# pot-boardB.net
KiCad netlist of a schematic drawn in EAGLE
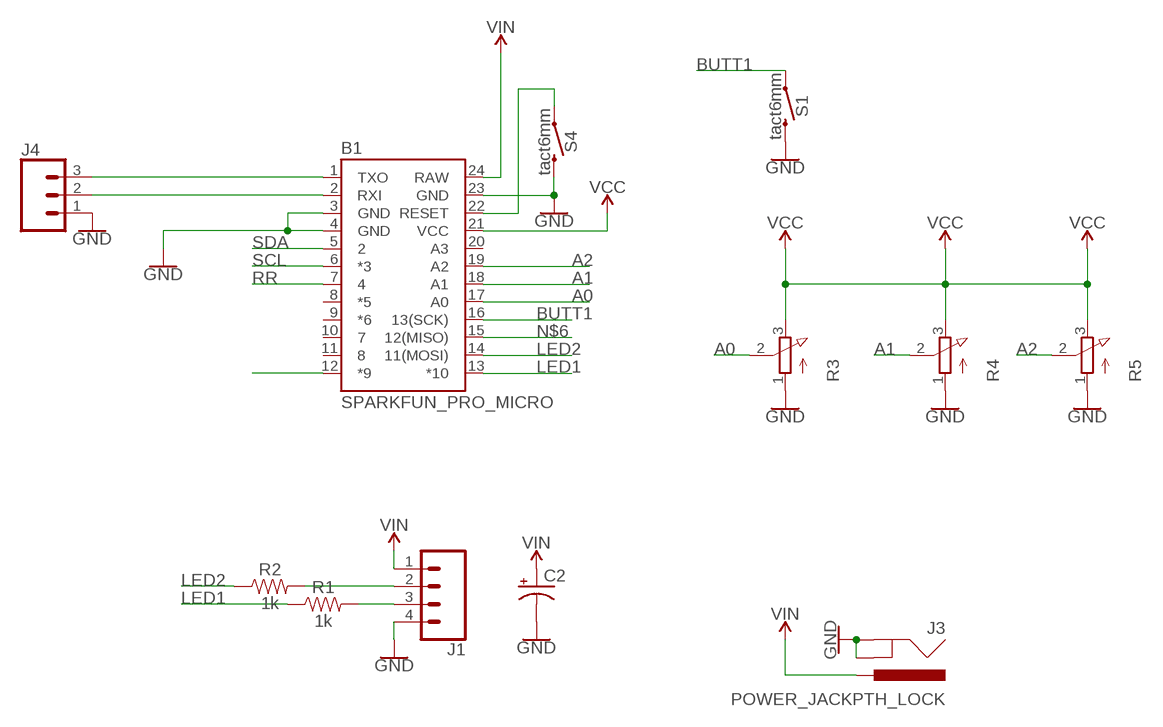
[diagram p0: schematic, sheet 1]

(export (version "E")
  (design (tool "Eeschema 10.0.6"))
  (components
    (comp (ref "B1")
      (value "SPARKFUN_PRO_MICRO")
      (footprint "eagle-import:SPARKFUN_PRO_MICRO")
      (libsource (lib "eagle-import") (part "SPARKFUN_PRO_MICRO"))
    )
    (comp (ref "C2")
      (value "CPOL-USE3.5-8")
      (footprint "eagle-import:E3,5-8")
      (libsource (lib "eagle-import") (part "CPOL-USE3.5-8"))
    )
    (comp (ref "J1")
      (value "CONN_04")
      (footprint "eagle-import:1X04")
      (libsource (lib "eagle-import") (part "CONN_04"))
    )
    (comp (ref "J3")
      (value "POWER_JACKPTH_LOCK")
      (footprint "eagle-import:POWER_JACK_PTH_LOCK")
      (libsource (lib "eagle-import") (part "POWER_JACKPTH_LOCK"))
    )
    (comp (ref "J4")
      (value "CONN_03")
      (footprint "eagle-import:1X03")
      (libsource (lib "eagle-import") (part "CONN_03"))
    )
    (comp (ref "R1")
      (value "1k")
      (footprint "eagle-import:AXIAL-0.3")
      (libsource (lib "eagle-import") (part "1KOHM-HORIZ-1/4W-5%"))
    )
    (comp (ref "R2")
      (value "1k")
      (footprint "eagle-import:AXIAL-0.3")
      (libsource (lib "eagle-import") (part "1KOHM-HORIZ-1/4W-5%"))
    )
    (comp (ref "R3")
      (value "3RP/1610N")
      (footprint "eagle-import:3RP_1610N")
      (libsource (lib "eagle-import") (part "3RP/1610N"))
    )
    (comp (ref "R4")
      (value "3RP/1610N")
      (footprint "eagle-import:3RP_1610N")
      (libsource (lib "eagle-import") (part "3RP/1610N"))
    )
    (comp (ref "R5")
      (value "3RP/1610N")
      (footprint "eagle-import:3RP_1610N")
      (libsource (lib "eagle-import") (part "3RP/1610N"))
    )
    (comp (ref "S1")
      (value "tact6mm")
      (footprint "eagle-import:TACTILE_SWITCH_PTH_6.0MM")
      (libsource (lib "eagle-import") (part "MOMENTARY-SWITCH-SPST-PTH-6.0MM"))
    )
    (comp (ref "S4")
      (value "tact6mm")
      (footprint "eagle-import:TACTILE_SWITCH_PTH_6.0MM")
      (libsource (lib "eagle-import") (part "MOMENTARY-SWITCH-SPST-PTH-6.0MM"))
    )
  )
  (nets
    (net (code "1") (name "/A0") (class "Default")
      (node (ref "B1") (pin "17") (pinfunction "A0_17") (pintype "bidirectional"))
      (node (ref "R3") (pin "2") (pinfunction "S_2") (pintype "passive"))
    )
    (net (code "2") (name "/A1") (class "Default")
      (node (ref "B1") (pin "18") (pinfunction "A1_18") (pintype "bidirectional"))
      (node (ref "R4") (pin "2") (pinfunction "S_2") (pintype "passive"))
    )
    (net (code "3") (name "/A2") (class "Default")
      (node (ref "B1") (pin "19") (pinfunction "A2_19") (pintype "bidirectional"))
      (node (ref "R5") (pin "2") (pinfunction "S_2") (pintype "passive"))
    )
    (net (code "4") (name "/BUTT1") (class "Default")
      (node (ref "B1") (pin "16") (pinfunction "13(SCK)_16") (pintype "bidirectional"))
      (node (ref "S1") (pin "1") (pinfunction "1_1") (pintype "passive"))
    )
    (net (code "5") (name "/LED1") (class "Default")
      (node (ref "B1") (pin "13") (pinfunction "*10_13") (pintype "bidirectional"))
      (node (ref "R1") (pin "P$1") (pinfunction "1_P$1") (pintype "passive"))
    )
    (net (code "6") (name "/LED2") (class "Default")
      (node (ref "B1") (pin "14") (pinfunction "11(MOSI)_14") (pintype "bidirectional"))
      (node (ref "R2") (pin "P$1") (pinfunction "1_P$1") (pintype "passive"))
    )
    (net (code "7") (name "/N$6") (class "Default")
      (node (ref "B1") (pin "15") (pinfunction "12(MISO)_15") (pintype "bidirectional"))
    )
    (net (code "8") (name "/RR") (class "Default")
      (node (ref "B1") (pin "7") (pinfunction "4_7") (pintype "bidirectional"))
    )
    (net (code "9") (name "/SCL") (class "Default")
      (node (ref "B1") (pin "6") (pinfunction "*3_6") (pintype "bidirectional"))
    )
    (net (code "10") (name "/SDA") (class "Default")
      (node (ref "B1") (pin "5") (pinfunction "2_5") (pintype "bidirectional"))
    )
    (net (code "11") (name "GND") (class "Default")
      (node (ref "B1") (pin "23") (pinfunction "GND_23") (pintype "power_in"))
      (node (ref "B1") (pin "3") (pinfunction "GND_3") (pintype "power_in"))
      (node (ref "B1") (pin "4") (pinfunction "GND_4") (pintype "power_in"))
      (node (ref "C2") (pin "-") (pinfunction "-_-") (pintype "passive"))
      (node (ref "J1") (pin "4") (pinfunction "4_4") (pintype "passive"))
      (node (ref "J3") (pin "GND") (pinfunction "GND_GND") (pintype "bidirectional"))
      (node (ref "J3") (pin "GNDBREAK") (pinfunction "GNDBREAK_GNDBREAK") (pintype "bidirectional"))
      (node (ref "J4") (pin "1") (pinfunction "1_1") (pintype "passive"))
      (node (ref "R3") (pin "1") (pinfunction "A_1") (pintype "passive"))
      (node (ref "R4") (pin "1") (pinfunction "A_1") (pintype "passive"))
      (node (ref "R5") (pin "1") (pinfunction "A_1") (pintype "passive"))
      (node (ref "S1") (pin "3") (pinfunction "2_3") (pintype "passive"))
      (node (ref "S4") (pin "3") (pinfunction "2_3") (pintype "passive"))
    )
    (net (code "12") (name "Net-(B1-RESET)") (class "Default")
      (node (ref "B1") (pin "22") (pinfunction "RESET_22") (pintype "bidirectional"))
      (node (ref "S4") (pin "1") (pinfunction "1_1") (pintype "passive"))
    )
    (net (code "13") (name "Net-(B1-RXI)") (class "Default")
      (node (ref "B1") (pin "2") (pinfunction "RXI_2") (pintype "bidirectional"))
      (node (ref "J4") (pin "2") (pinfunction "2_2") (pintype "passive"))
    )
    (net (code "14") (name "Net-(B1-TXO)") (class "Default")
      (node (ref "B1") (pin "1") (pinfunction "TXO_1") (pintype "bidirectional"))
      (node (ref "J4") (pin "3") (pinfunction "3_3") (pintype "passive"))
    )
    (net (code "15") (name "Net-(R1-2)") (class "Default")
      (node (ref "J1") (pin "3") (pinfunction "3_3") (pintype "passive"))
      (node (ref "R1") (pin "P$2") (pinfunction "2_P$2") (pintype "passive"))
    )
    (net (code "16") (name "Net-(R2-2)") (class "Default")
      (node (ref "J1") (pin "2") (pinfunction "2_2") (pintype "passive"))
      (node (ref "R2") (pin "P$2") (pinfunction "2_P$2") (pintype "passive"))
    )
    (net (code "17") (name "VCC") (class "Default")
      (node (ref "B1") (pin "21") (pinfunction "VCC_21") (pintype "power_in"))
      (node (ref "R3") (pin "3") (pinfunction "E_3") (pintype "passive"))
      (node (ref "R4") (pin "3") (pinfunction "E_3") (pintype "passive"))
      (node (ref "R5") (pin "3") (pinfunction "E_3") (pintype "passive"))
    )
    (net (code "18") (name "VIN") (class "Default")
      (node (ref "B1") (pin "24") (pinfunction "RAW_24") (pintype "power_in"))
      (node (ref "C2") (pin "+") (pinfunction "+_+") (pintype "passive"))
      (node (ref "J1") (pin "1") (pinfunction "1_1") (pintype "passive"))
      (node (ref "J3") (pin "PWR") (pinfunction "PWR_PWR") (pintype "bidirectional"))
    )
    (net (code "19") (name "unconnected-(B1-*5-Pad8)") (class "Default")
      (node (ref "B1") (pin "8") (pinfunction "*5_8") (pintype "bidirectional"))
    )
    (net (code "20") (name "unconnected-(B1-*6-Pad9)") (class "Default")
      (node (ref "B1") (pin "9") (pinfunction "*6_9") (pintype "bidirectional"))
    )
    (net (code "21") (name "unconnected-(B1-*9-Pad12)") (class "Default")
      (node (ref "B1") (pin "12") (pinfunction "*9_12") (pintype "bidirectional"))
    )
    (net (code "22") (name "unconnected-(B1-7-Pad10)") (class "Default")
      (node (ref "B1") (pin "10") (pinfunction "7_10") (pintype "bidirectional"))
    )
    (net (code "23") (name "unconnected-(B1-8-Pad11)") (class "Default")
      (node (ref "B1") (pin "11") (pinfunction "8_11") (pintype "bidirectional"))
    )
    (net (code "24") (name "unconnected-(B1-A3-Pad20)") (class "Default")
      (node (ref "B1") (pin "20") (pinfunction "A3_20") (pintype "bidirectional"))
    )
  )
)
